# ampli_auriculares.net
KiCad netlist of a schematic drawn in EAGLE
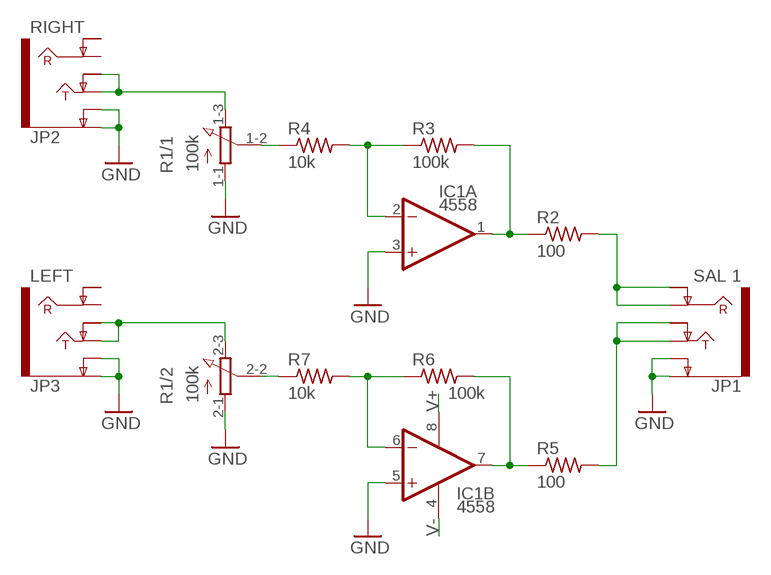
[diagram p0: schematic, sheet 1]
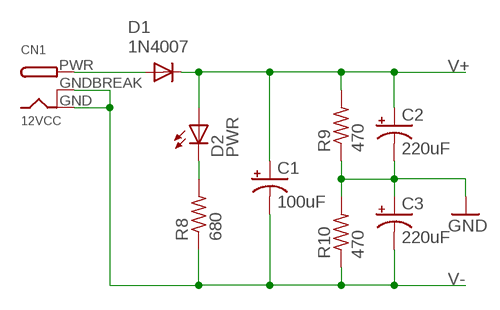
[diagram p1: schematic, sheet 2]

(export (version "E")
  (design (tool "Eeschema 10.0.6"))
  (components
    (comp (ref "IC1")
      (value "4558")
      (footprint "eagle-import:DIL08")
      (libsource (lib "eagle-import") (part "1458NLM"))
    )
    (comp (ref "JP1")
      (value "SAL 1")
      (footprint "eagle-import:AUDIO-JACK-.25-INCH-HORIZ-PTH")
      (libsource (lib "eagle-import") (part "AUDIO-JACK4-.25-HORIZ-TRS"))
    )
    (comp (ref "JP2")
      (value "RIGHT")
      (footprint "eagle-import:AUDIO-JACK-.25-INCH-HORIZ-PTH")
      (libsource (lib "eagle-import") (part "AUDIO-JACK4-.25-HORIZ-TRS"))
    )
    (comp (ref "JP3")
      (value "LEFT")
      (footprint "eagle-import:AUDIO-JACK-.25-INCH-HORIZ-PTH")
      (libsource (lib "eagle-import") (part "AUDIO-JACK4-.25-HORIZ-TRS"))
    )
    (comp (ref "R1")
      (value "100k")
      (footprint "eagle-import:3RP_1610G")
      (libsource (lib "eagle-import") (part "3RP/1610G"))
    )
    (comp (ref "R2")
      (value "100")
      (footprint "eagle-import:0204_7")
      (libsource (lib "eagle-import") (part "R-US_0204/7"))
    )
    (comp (ref "R3")
      (value "100k")
      (footprint "eagle-import:0204_7")
      (libsource (lib "eagle-import") (part "R-US_0204/7"))
    )
    (comp (ref "R4")
      (value "10k")
      (footprint "eagle-import:0204_7")
      (libsource (lib "eagle-import") (part "R-US_0204/7"))
    )
    (comp (ref "R5")
      (value "100")
      (footprint "eagle-import:0204_7")
      (libsource (lib "eagle-import") (part "R-US_0204/7"))
    )
    (comp (ref "R6")
      (value "100k")
      (footprint "eagle-import:0204_7")
      (libsource (lib "eagle-import") (part "R-US_0204/7"))
    )
    (comp (ref "R7")
      (value "10k")
      (footprint "eagle-import:0204_7")
      (libsource (lib "eagle-import") (part "R-US_0204/7"))
    )
    (comp (ref "C1")
      (value "100uF")
      (footprint "eagle-import:E2,5-6")
      (libsource (lib "eagle-import") (part "CPOL-USE2.5-6"))
    )
    (comp (ref "C2")
      (value "220uF")
      (footprint "eagle-import:E2,5-6")
      (libsource (lib "eagle-import") (part "CPOL-USE2.5-6"))
    )
    (comp (ref "C3")
      (value "220uF")
      (footprint "eagle-import:E2,5-6")
      (libsource (lib "eagle-import") (part "CPOL-USE2.5-6"))
    )
    (comp (ref "CN1")
      (value "12VCC")
      (footprint "eagle-import:DCJACK_2MM_PTH")
      (libsource (lib "eagle-import") (part "DCBARRELPTH"))
    )
    (comp (ref "D1")
      (value "1N4007")
      (footprint "eagle-import:DO41-10")
      (libsource (lib "eagle-import") (part "1N4004"))
    )
    (comp (ref "D2")
      (value "PWR")
      (footprint "eagle-import:LED3MM")
      (libsource (lib "eagle-import") (part "LED3MM"))
    )
    (comp (ref "R8")
      (value "680")
      (footprint "eagle-import:0204_7")
      (libsource (lib "eagle-import") (part "R-US_0204/7"))
    )
    (comp (ref "R9")
      (value "470")
      (footprint "eagle-import:0207_10")
      (libsource (lib "eagle-import") (part "R-US_0207/10"))
    )
    (comp (ref "R10")
      (value "470")
      (footprint "eagle-import:0207_10")
      (libsource (lib "eagle-import") (part "R-US_0207/10"))
    )
  )
  (nets
    (net (code "1") (name "GND") (class "Default")
      (node (ref "C2") (pin "-") (pinfunction "-_-") (pintype "passive"))
      (node (ref "C3") (pin "+") (pinfunction "+_+") (pintype "passive"))
      (node (ref "IC1") (pin "3") (pinfunction "+IN_3") (pintype "input"))
      (node (ref "IC1") (pin "5") (pinfunction "+IN_5") (pintype "input"))
      (node (ref "JP1") (pin "SLEEVE") (pinfunction "EARTH_SLEEVE") (pintype "bidirectional"))
      (node (ref "JP1") (pin "SLEEVE-NORM") (pinfunction "EARTH-NORM_SLEEVE-NORM") (pintype "bidirectional"))
      (node (ref "JP2") (pin "SLEEVE") (pinfunction "EARTH_SLEEVE") (pintype "bidirectional"))
      (node (ref "JP2") (pin "SLEEVE-NORM") (pinfunction "EARTH-NORM_SLEEVE-NORM") (pintype "bidirectional"))
      (node (ref "JP3") (pin "SLEEVE") (pinfunction "EARTH_SLEEVE") (pintype "bidirectional"))
      (node (ref "JP3") (pin "SLEEVE-NORM") (pinfunction "EARTH-NORM_SLEEVE-NORM") (pintype "bidirectional"))
      (node (ref "R1") (pin "1-1") (pinfunction "A_1-1") (pintype "passive"))
      (node (ref "R1") (pin "2-1") (pinfunction "A_2-1") (pintype "passive"))
      (node (ref "R10") (pin "2") (pinfunction "2_2") (pintype "passive"))
      (node (ref "R9") (pin "1") (pinfunction "1_1") (pintype "passive"))
    )
    (net (code "2") (name "Net-(CN1-PadPWR)") (class "Default")
      (node (ref "CN1") (pin "PWR") (pinfunction "PWR_PWR") (pintype "power_in"))
      (node (ref "D1") (pin "A") (pinfunction "A_A") (pintype "passive"))
    )
    (net (code "3") (name "Net-(D2-C)") (class "Default")
      (node (ref "D2") (pin "K") (pinfunction "C_K") (pintype "passive"))
      (node (ref "R8") (pin "2") (pinfunction "2_2") (pintype "passive"))
    )
    (net (code "4") (name "Net-(IC1A--IN)") (class "Default")
      (node (ref "IC1") (pin "2") (pinfunction "-IN_2") (pintype "input"))
      (node (ref "R3") (pin "1") (pinfunction "1_1") (pintype "passive"))
      (node (ref "R4") (pin "2") (pinfunction "2_2") (pintype "passive"))
    )
    (net (code "5") (name "Net-(IC1A-OUT)") (class "Default")
      (node (ref "IC1") (pin "1") (pinfunction "OUT_1") (pintype "output"))
      (node (ref "R2") (pin "1") (pinfunction "1_1") (pintype "passive"))
      (node (ref "R3") (pin "2") (pinfunction "2_2") (pintype "passive"))
    )
    (net (code "6") (name "Net-(IC1B--IN)") (class "Default")
      (node (ref "IC1") (pin "6") (pinfunction "-IN_6") (pintype "input"))
      (node (ref "R6") (pin "1") (pinfunction "1_1") (pintype "passive"))
      (node (ref "R7") (pin "2") (pinfunction "2_2") (pintype "passive"))
    )
    (net (code "7") (name "Net-(IC1B-OUT)") (class "Default")
      (node (ref "IC1") (pin "7") (pinfunction "OUT_7") (pintype "output"))
      (node (ref "R5") (pin "1") (pinfunction "1_1") (pintype "passive"))
      (node (ref "R6") (pin "2") (pinfunction "2_2") (pintype "passive"))
    )
    (net (code "8") (name "Net-(JP1-PadRING)") (class "Default")
      (node (ref "JP1") (pin "RING") (pinfunction "RING_RING") (pintype "bidirectional"))
      (node (ref "JP1") (pin "RING-NORM") (pinfunction "RING-NORM_RING-NORM") (pintype "bidirectional"))
      (node (ref "R2") (pin "2") (pinfunction "2_2") (pintype "passive"))
    )
    (net (code "9") (name "Net-(JP1-PadTIP)") (class "Default")
      (node (ref "JP1") (pin "TIP") (pinfunction "TIP_TIP") (pintype "bidirectional"))
      (node (ref "JP1") (pin "TIP-NORM") (pinfunction "TIP-NORM_TIP-NORM") (pintype "bidirectional"))
      (node (ref "R5") (pin "2") (pinfunction "2_2") (pintype "passive"))
    )
    (net (code "10") (name "Net-(R1A-E)") (class "Default")
      (node (ref "JP2") (pin "TIP") (pinfunction "TIP_TIP") (pintype "bidirectional"))
      (node (ref "JP2") (pin "TIP-NORM") (pinfunction "TIP-NORM_TIP-NORM") (pintype "bidirectional"))
      (node (ref "R1") (pin "1-3") (pinfunction "E_1-3") (pintype "passive"))
    )
    (net (code "11") (name "Net-(R1A-S)") (class "Default")
      (node (ref "R1") (pin "1-2") (pinfunction "S_1-2") (pintype "passive"))
      (node (ref "R4") (pin "1") (pinfunction "1_1") (pintype "passive"))
    )
    (net (code "12") (name "Net-(R1B-E)") (class "Default")
      (node (ref "JP3") (pin "TIP") (pinfunction "TIP_TIP") (pintype "bidirectional"))
      (node (ref "JP3") (pin "TIP-NORM") (pinfunction "TIP-NORM_TIP-NORM") (pintype "bidirectional"))
      (node (ref "R1") (pin "2-3") (pinfunction "E_2-3") (pintype "passive"))
    )
    (net (code "13") (name "Net-(R1B-S)") (class "Default")
      (node (ref "R1") (pin "2-2") (pinfunction "S_2-2") (pintype "passive"))
      (node (ref "R7") (pin "1") (pinfunction "1_1") (pintype "passive"))
    )
    (net (code "14") (name "V+") (class "Default")
      (node (ref "C1") (pin "+") (pinfunction "+_+") (pintype "passive"))
      (node (ref "C2") (pin "+") (pinfunction "+_+") (pintype "passive"))
      (node (ref "D1") (pin "C") (pinfunction "C_C") (pintype "passive"))
      (node (ref "D2") (pin "A") (pinfunction "A_A") (pintype "passive"))
      (node (ref "IC1") (pin "8") (pinfunction "V+_8") (pintype "power_in"))
      (node (ref "R9") (pin "2") (pinfunction "2_2") (pintype "passive"))
    )
    (net (code "15") (name "V-") (class "Default")
      (node (ref "C1") (pin "-") (pinfunction "-_-") (pintype "passive"))
      (node (ref "C3") (pin "-") (pinfunction "-_-") (pintype "passive"))
      (node (ref "CN1") (pin "GND") (pinfunction "GND_GND") (pintype "power_in"))
      (node (ref "CN1") (pin "GNDBREAK") (pinfunction "GNDBREAK_GNDBREAK") (pintype "power_in"))
      (node (ref "IC1") (pin "4") (pinfunction "V-_4") (pintype "power_in"))
      (node (ref "R10") (pin "1") (pinfunction "1_1") (pintype "passive"))
      (node (ref "R8") (pin "1") (pinfunction "1_1") (pintype "passive"))
    )
    (net (code "16") (name "unconnected-(JP2-PadRING)") (class "Default")
      (node (ref "JP2") (pin "RING") (pinfunction "RING_RING") (pintype "bidirectional"))
    )
    (net (code "17") (name "unconnected-(JP2-PadRING-NORM)") (class "Default")
      (node (ref "JP2") (pin "RING-NORM") (pinfunction "RING-NORM_RING-NORM") (pintype "bidirectional"))
    )
    (net (code "18") (name "unconnected-(JP3-PadRING)") (class "Default")
      (node (ref "JP3") (pin "RING") (pinfunction "RING_RING") (pintype "bidirectional"))
    )
    (net (code "19") (name "unconnected-(JP3-PadRING-NORM)") (class "Default")
      (node (ref "JP3") (pin "RING-NORM") (pinfunction "RING-NORM_RING-NORM") (pintype "bidirectional"))
    )
  )
)
